# aux_power.net
KiCad netlist of a schematic drawn in Altium Designer
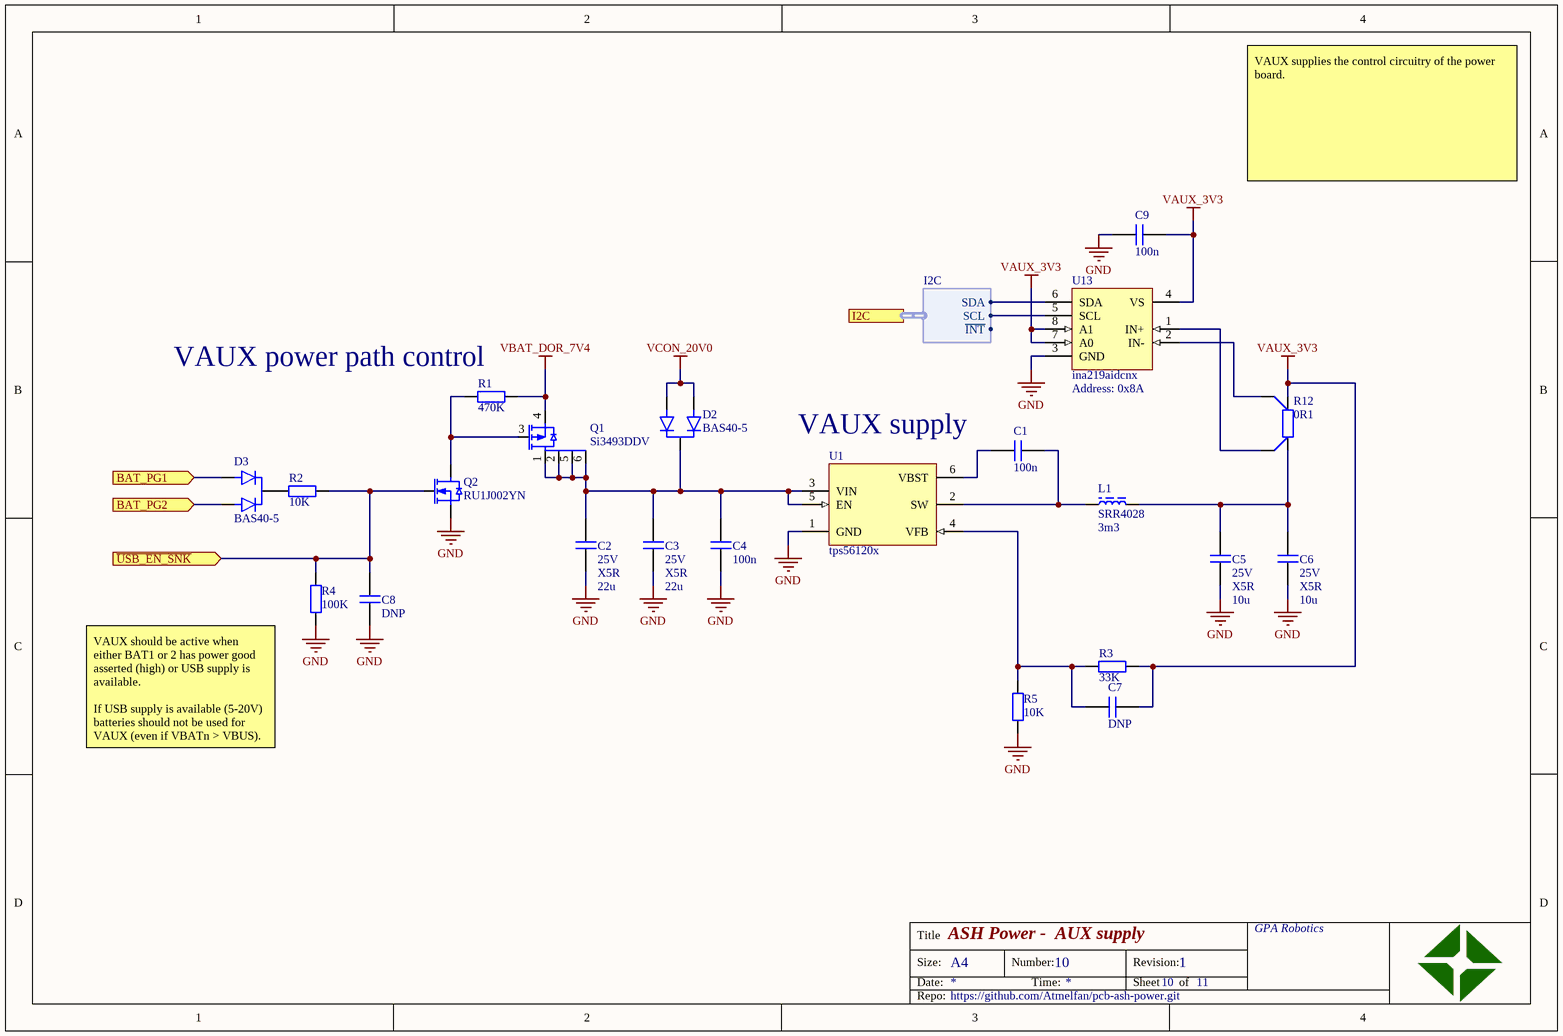
[diagram p0: aux_power.SchDoc]

(export (version "E")
  (design (tool "Eeschema 10.0.6"))
  (components
    (comp (ref "C1")
      (value "100n")
      (footprint "CAPC1005X06N")
      (description "Capacitor")
      (fields (field (name "Comment") "cap"))
      (libsource (lib "lib_passives") (part "cap"))
    )
    (comp (ref "C2")
      (value "22u")
      (footprint "CAPC3216X14N")
      (description "Capacitor")
      (fields (field (name "VOLTAGE") "25V") (field (name "TYPE") "X5R") (field (name "Comment") "cap"))
      (libsource (lib "lib_passives") (part "cap"))
    )
    (comp (ref "C3")
      (value "22u")
      (footprint "CAPC3216X14N")
      (description "Capacitor")
      (fields (field (name "VOLTAGE") "25V") (field (name "TYPE") "X5R") (field (name "Comment") "cap"))
      (libsource (lib "lib_passives") (part "cap"))
    )
    (comp (ref "C4")
      (value "100n")
      (footprint "CAPC1005X06N")
      (description "Capacitor")
      (fields (field (name "Comment") "cap"))
      (libsource (lib "lib_passives") (part "cap"))
    )
    (comp (ref "C5")
      (value "10u")
      (footprint "CAPC3216X14N")
      (description "Capacitor")
      (fields (field (name "VOLTAGE") "25V") (field (name "TYPE") "X5R") (field (name "Comment") "cap"))
      (libsource (lib "lib_passives") (part "cap"))
    )
    (comp (ref "C6")
      (value "10u")
      (footprint "CAPC3216X14N")
      (description "Capacitor")
      (fields (field (name "VOLTAGE") "25V") (field (name "TYPE") "X5R") (field (name "Comment") "cap"))
      (libsource (lib "lib_passives") (part "cap"))
    )
    (comp (ref "C7")
      (value "DNP")
      (footprint "CAPC1005X06N")
      (description "Capacitor")
      (fields (field (name "Comment") "cap"))
      (libsource (lib "lib_passives") (part "cap"))
    )
    (comp (ref "C8")
      (value "DNP")
      (footprint "CAPC1005X06N")
      (description "Capacitor")
      (fields (field (name "Comment") "cap"))
      (libsource (lib "lib_passives") (part "cap"))
    )
    (comp (ref "C9")
      (value "100n")
      (footprint "CAPC1005X06N")
      (description "Capacitor")
      (fields (field (name "Comment") "cap"))
      (libsource (lib "lib_passives") (part "cap"))
    )
    (comp (ref "D2")
      (value "BAS40-5")
      (footprint "SOT23_CC")
      (description "Diode Common Cathode")
      (libsource (lib "lib_actives") (part "diode_dual_cc"))
    )
    (comp (ref "D3")
      (value "BAS40-5")
      (footprint "SOT23_CC")
      (description "Diode Common Cathode")
      (libsource (lib "lib_actives") (part "diode_dual_cc"))
    )
    (comp (ref "L1")
      (value "SRR4028")
      (footprint "SRR4028")
      (fields (field (name "ALTIUM_VALUE") "3m3"))
      (libsource (lib "lib_bourns") (part "srr4028"))
    )
    (comp (ref "Q1")
      (value "Si3493DDV")
      (footprint "SOT95P284X110-6N_TSOP6")
      (description "P-Channel 20 V (D-S) MOSFET")
      (libsource (lib "lib_vishay") (part "si3493ddv"))
    )
    (comp (ref "Q2")
      (value "RU1J002YN")
      (footprint "SOTFL65P210X105-3N")
      (description "N-channel 50V 200mA Small signal MOSFET")
      (libsource (lib "lib_rohm") (part "ru1j002yn"))
    )
    (comp (ref "R1")
      (value "470K")
      (footprint "RESC1005X04N")
      (description "Resistor")
      (fields (field (name "Comment") "res"))
      (libsource (lib "") (part "res_1"))
    )
    (comp (ref "R2")
      (value "10K")
      (footprint "RESC1005X04N")
      (description "Resistor")
      (fields (field (name "Comment") "res"))
      (libsource (lib "") (part "res_1"))
    )
    (comp (ref "R3")
      (value "33K")
      (footprint "RESC1005X04N")
      (description "Resistor")
      (fields (field (name "Comment") "res"))
      (libsource (lib "") (part "res_1"))
    )
    (comp (ref "R4")
      (value "100K")
      (footprint "RESC1005X04N")
      (description "Resistor")
      (fields (field (name "Comment") "res"))
      (libsource (lib "lib_passives") (part "res"))
    )
    (comp (ref "R5")
      (value "10K")
      (footprint "RESC1005X04N")
      (description "Resistor")
      (fields (field (name "Comment") "res"))
      (libsource (lib "lib_passives") (part "res"))
    )
    (comp (ref "R12")
      (value "0R1")
      (footprint "RESC2012X06N_4T")
      (description "Resistor")
      (fields (field (name "Comment") "res_4t"))
      (libsource (lib "lib_passives") (part "res_4t"))
    )
    (comp (ref "U1")
      (value "tps56120x")
      (footprint "SOT95P280X110-6N")
      (description "4.5-V to 17-V Input, 1-A Synchronous  Step-Down  Voltage  Regulator  in 6-Pin  SOT-23")
      (libsource (lib "lib_ti") (part "tps56120x"))
    )
    (comp (ref "U13")
      (value "ina219aidcnx")
      (footprint "TSOP65P280X145-8N")
      (description "INA219 Zero-Drift, Bidirectional Current/Power Monitor With I2C Interface")
      (fields (field (name "ADDRESS") "0x8A"))
      (libsource (lib "lib_ti") (part "ina219aidcnx"))
    )
  )
  (nets
    (net (code "2") (name "/BAT_PG1") (class "Default")
      (node (ref "D3") (pin "A1") (pinfunction "A1_A1") (pintype "passive"))
    )
    (net (code "3") (name "/BAT_PG2") (class "Default")
      (node (ref "D3") (pin "A2") (pinfunction "A2_A2") (pintype "passive"))
    )
    (net (code "4") (name "/SCL") (class "Default")
      (node (ref "U13") (pin "5") (pinfunction "SCL_5") (pintype "open_collector"))
    )
    (net (code "5") (name "/SDA") (class "Default")
      (node (ref "U13") (pin "6") (pinfunction "SDA_6") (pintype "open_collector"))
    )
    (net (code "6") (name "/USB_EN_SNK") (class "Default")
      (node (ref "C8") (pin "2") (pinfunction "2_2") (pintype "passive"))
      (node (ref "Q2") (pin "1") (pinfunction "G_1") (pintype "passive"))
      (node (ref "R2") (pin "2") (pinfunction "2_2") (pintype "passive"))
      (node (ref "R4") (pin "2") (pinfunction "2_2") (pintype "passive"))
    )
    (net (code "8") (name "GND") (class "Default")
      (node (ref "C2") (pin "1") (pinfunction "1_1") (pintype "passive"))
      (node (ref "C3") (pin "1") (pinfunction "1_1") (pintype "passive"))
      (node (ref "C4") (pin "1") (pinfunction "1_1") (pintype "passive"))
      (node (ref "C5") (pin "1") (pinfunction "1_1") (pintype "passive"))
      (node (ref "C6") (pin "1") (pinfunction "1_1") (pintype "passive"))
      (node (ref "C8") (pin "1") (pinfunction "1_1") (pintype "passive"))
      (node (ref "C9") (pin "2") (pinfunction "2_2") (pintype "passive"))
      (node (ref "Q2") (pin "2") (pinfunction "S_2") (pintype "passive"))
      (node (ref "R4") (pin "1") (pinfunction "1_1") (pintype "passive"))
      (node (ref "R5") (pin "1") (pinfunction "1_1") (pintype "passive"))
      (node (ref "U1") (pin "1") (pinfunction "GND_1") (pintype "power_in"))
      (node (ref "U13") (pin "3") (pinfunction "GND_3") (pintype "power_in"))
    )
    (net (code "9") (name "Net-(C5-Pad2)") (class "Default")
      (node (ref "C5") (pin "2") (pinfunction "2_2") (pintype "passive"))
      (node (ref "C6") (pin "2") (pinfunction "2_2") (pintype "passive"))
      (node (ref "L1") (pin "2") (pinfunction "2_2") (pintype "passive"))
      (node (ref "R12") (pin "2") (pinfunction "2_2") (pintype "passive"))
    )
    (net (code "10") (name "Net-(D3-PadC)") (class "Default")
      (node (ref "D3") (pin "C") (pinfunction "C_C") (pintype "passive"))
      (node (ref "R2") (pin "1") (pinfunction "1_1") (pintype "passive"))
    )
    (net (code "11") (name "Net-(Q1-G)") (class "Default")
      (node (ref "Q1") (pin "3") (pinfunction "G_3") (pintype "passive"))
      (node (ref "Q2") (pin "3") (pinfunction "D_3") (pintype "passive"))
      (node (ref "R1") (pin "1") (pinfunction "1_1") (pintype "passive"))
    )
    (net (code "12") (name "Net-(U1-EN)") (class "Default")
      (node (ref "C2") (pin "2") (pinfunction "2_2") (pintype "passive"))
      (node (ref "C3") (pin "2") (pinfunction "2_2") (pintype "passive"))
      (node (ref "C4") (pin "2") (pinfunction "2_2") (pintype "passive"))
      (node (ref "D2") (pin "C") (pinfunction "C_C") (pintype "passive"))
      (node (ref "Q1") (pin "1") (pinfunction "D_1") (pintype "passive"))
      (node (ref "Q1") (pin "2") (pinfunction "D_2") (pintype "passive"))
      (node (ref "Q1") (pin "5") (pinfunction "D_5") (pintype "passive"))
      (node (ref "Q1") (pin "6") (pinfunction "D_6") (pintype "passive"))
      (node (ref "U1") (pin "3") (pinfunction "VIN_3") (pintype "power_in"))
      (node (ref "U1") (pin "5") (pinfunction "EN_5") (pintype "input"))
    )
    (net (code "13") (name "Net-(U1-SW)") (class "Default")
      (node (ref "C1") (pin "2") (pinfunction "2_2") (pintype "passive"))
      (node (ref "L1") (pin "1") (pinfunction "1_1") (pintype "passive"))
      (node (ref "U1") (pin "2") (pinfunction "SW_2") (pintype "power_in"))
    )
    (net (code "14") (name "Net-(U1-VBST)") (class "Default")
      (node (ref "C1") (pin "1") (pinfunction "1_1") (pintype "passive"))
      (node (ref "U1") (pin "6") (pinfunction "VBST_6") (pintype "passive"))
    )
    (net (code "15") (name "Net-(U1-VFB)") (class "Default")
      (node (ref "C7") (pin "1") (pinfunction "1_1") (pintype "passive"))
      (node (ref "R3") (pin "1") (pinfunction "1_1") (pintype "passive"))
      (node (ref "R5") (pin "2") (pinfunction "2_2") (pintype "passive"))
      (node (ref "U1") (pin "4") (pinfunction "VFB_4") (pintype "input"))
    )
    (net (code "16") (name "Net-(U13-IN+)") (class "Default")
      (node (ref "R12") (pin "4") (pinfunction "4_4") (pintype "passive"))
      (node (ref "U13") (pin "1") (pinfunction "IN+_1") (pintype "input"))
    )
    (net (code "17") (name "Net-(U13-IN-)") (class "Default")
      (node (ref "R12") (pin "3") (pinfunction "3_3") (pintype "passive"))
      (node (ref "U13") (pin "2") (pinfunction "IN-_2") (pintype "input"))
    )
    (net (code "18") (name "VAUX_3V3") (class "Default")
      (node (ref "C7") (pin "2") (pinfunction "2_2") (pintype "passive"))
      (node (ref "C9") (pin "1") (pinfunction "1_1") (pintype "passive"))
      (node (ref "R12") (pin "1") (pinfunction "1_1") (pintype "passive"))
      (node (ref "R3") (pin "2") (pinfunction "2_2") (pintype "passive"))
      (node (ref "U13") (pin "4") (pinfunction "VS_4") (pintype "power_in"))
      (node (ref "U13") (pin "7") (pinfunction "A0_7") (pintype "input"))
      (node (ref "U13") (pin "8") (pinfunction "A1_8") (pintype "input"))
    )
    (net (code "19") (name "VBAT_DOR_7V4") (class "Default")
      (node (ref "Q1") (pin "4") (pinfunction "S_4") (pintype "passive"))
      (node (ref "R1") (pin "2") (pinfunction "2_2") (pintype "passive"))
    )
    (net (code "20") (name "VCON_20V0") (class "Default")
      (node (ref "D2") (pin "A1") (pinfunction "A1_A1") (pintype "passive"))
      (node (ref "D2") (pin "A2") (pinfunction "A2_A2") (pintype "passive"))
    )
  )
)
